# ow.net
KiCad netlist of a schematic drawn in EAGLE
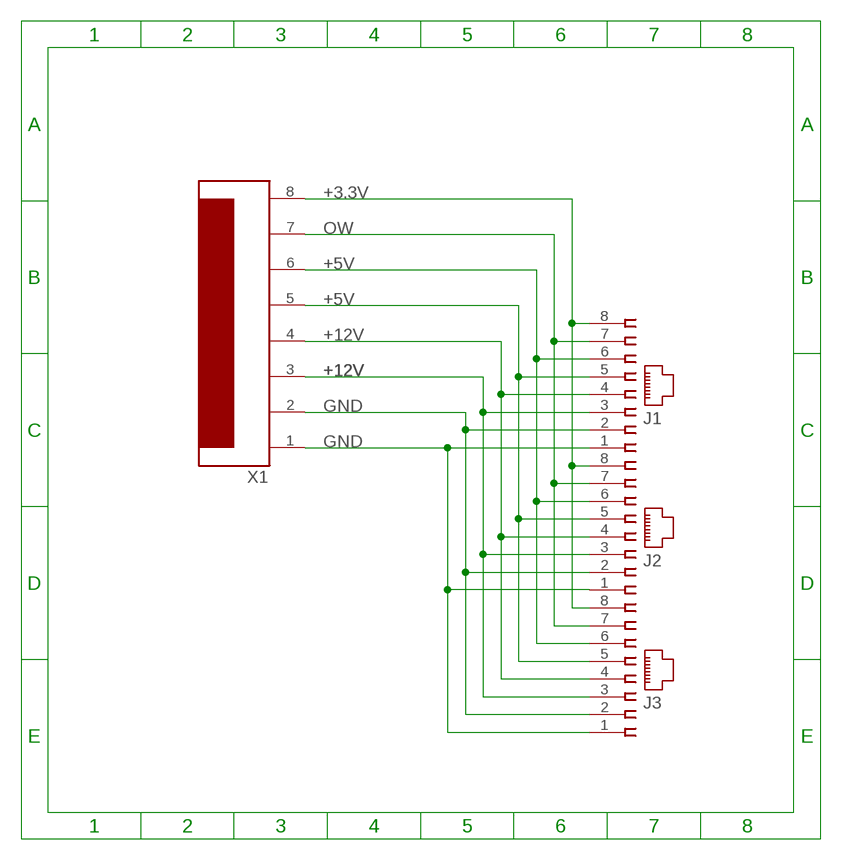
[diagram p0: schematic, sheet 1]

(export (version "E")
  (design (tool "Eeschema 10.0.6"))
  (components
    (comp (ref "J1")
      (value "215877-4")
      (footprint "eagle-import:215877-4")
      (libsource (lib "eagle-import") (part "215877-4"))
    )
    (comp (ref "J2")
      (value "215877-4")
      (footprint "eagle-import:215877-4")
      (libsource (lib "eagle-import") (part "215877-4"))
    )
    (comp (ref "J3")
      (value "215877-4")
      (footprint "eagle-import:215877-4")
      (libsource (lib "eagle-import") (part "215877-4"))
    )
    (comp (ref "X1")
      (value "1WIRE-CON")
      (footprint "eagle-import:KK-156-8")
      (libsource (lib "eagle-import") (part "1WIRE-CON"))
    )
  )
  (nets
    (net (code "1") (name "/+3.3V") (class "Default")
      (node (ref "J1") (pin "8") (pinfunction "8_8") (pintype "passive"))
      (node (ref "J2") (pin "8") (pinfunction "8_8") (pintype "passive"))
      (node (ref "J3") (pin "8") (pinfunction "8_8") (pintype "passive"))
      (node (ref "X1") (pin "8") (pinfunction "P$8_8") (pintype "bidirectional"))
    )
    (net (code "2") (name "/+5V") (class "Default")
      (node (ref "J1") (pin "5") (pinfunction "5_5") (pintype "passive"))
      (node (ref "J1") (pin "6") (pinfunction "6_6") (pintype "passive"))
      (node (ref "J2") (pin "5") (pinfunction "5_5") (pintype "passive"))
      (node (ref "J2") (pin "6") (pinfunction "6_6") (pintype "passive"))
      (node (ref "J3") (pin "5") (pinfunction "5_5") (pintype "passive"))
      (node (ref "J3") (pin "6") (pinfunction "6_6") (pintype "passive"))
      (node (ref "X1") (pin "5") (pinfunction "P$5_5") (pintype "bidirectional"))
      (node (ref "X1") (pin "6") (pinfunction "P$6_6") (pintype "bidirectional"))
    )
    (net (code "3") (name "/+12V") (class "Default")
      (node (ref "J1") (pin "3") (pinfunction "3_3") (pintype "passive"))
      (node (ref "J1") (pin "4") (pinfunction "4_4") (pintype "passive"))
      (node (ref "J2") (pin "3") (pinfunction "3_3") (pintype "passive"))
      (node (ref "J2") (pin "4") (pinfunction "4_4") (pintype "passive"))
      (node (ref "J3") (pin "3") (pinfunction "3_3") (pintype "passive"))
      (node (ref "J3") (pin "4") (pinfunction "4_4") (pintype "passive"))
      (node (ref "X1") (pin "3") (pinfunction "P$3_3") (pintype "bidirectional"))
      (node (ref "X1") (pin "4") (pinfunction "P$4_4") (pintype "bidirectional"))
    )
    (net (code "4") (name "/GND") (class "Default")
      (node (ref "J1") (pin "1") (pinfunction "1_1") (pintype "passive"))
      (node (ref "J1") (pin "2") (pinfunction "2_2") (pintype "passive"))
      (node (ref "J2") (pin "1") (pinfunction "1_1") (pintype "passive"))
      (node (ref "J2") (pin "2") (pinfunction "2_2") (pintype "passive"))
      (node (ref "J3") (pin "1") (pinfunction "1_1") (pintype "passive"))
      (node (ref "J3") (pin "2") (pinfunction "2_2") (pintype "passive"))
      (node (ref "X1") (pin "1") (pinfunction "P$1_1") (pintype "bidirectional"))
      (node (ref "X1") (pin "2") (pinfunction "P$2_2") (pintype "bidirectional"))
    )
    (net (code "5") (name "/OW") (class "Default")
      (node (ref "J1") (pin "7") (pinfunction "7_7") (pintype "passive"))
      (node (ref "J2") (pin "7") (pinfunction "7_7") (pintype "passive"))
      (node (ref "J3") (pin "7") (pinfunction "7_7") (pintype "passive"))
      (node (ref "X1") (pin "7") (pinfunction "P$7_7") (pintype "bidirectional"))
    )
  )
)
